# versao1.net
KiCad netlist of a schematic drawn in EAGLE
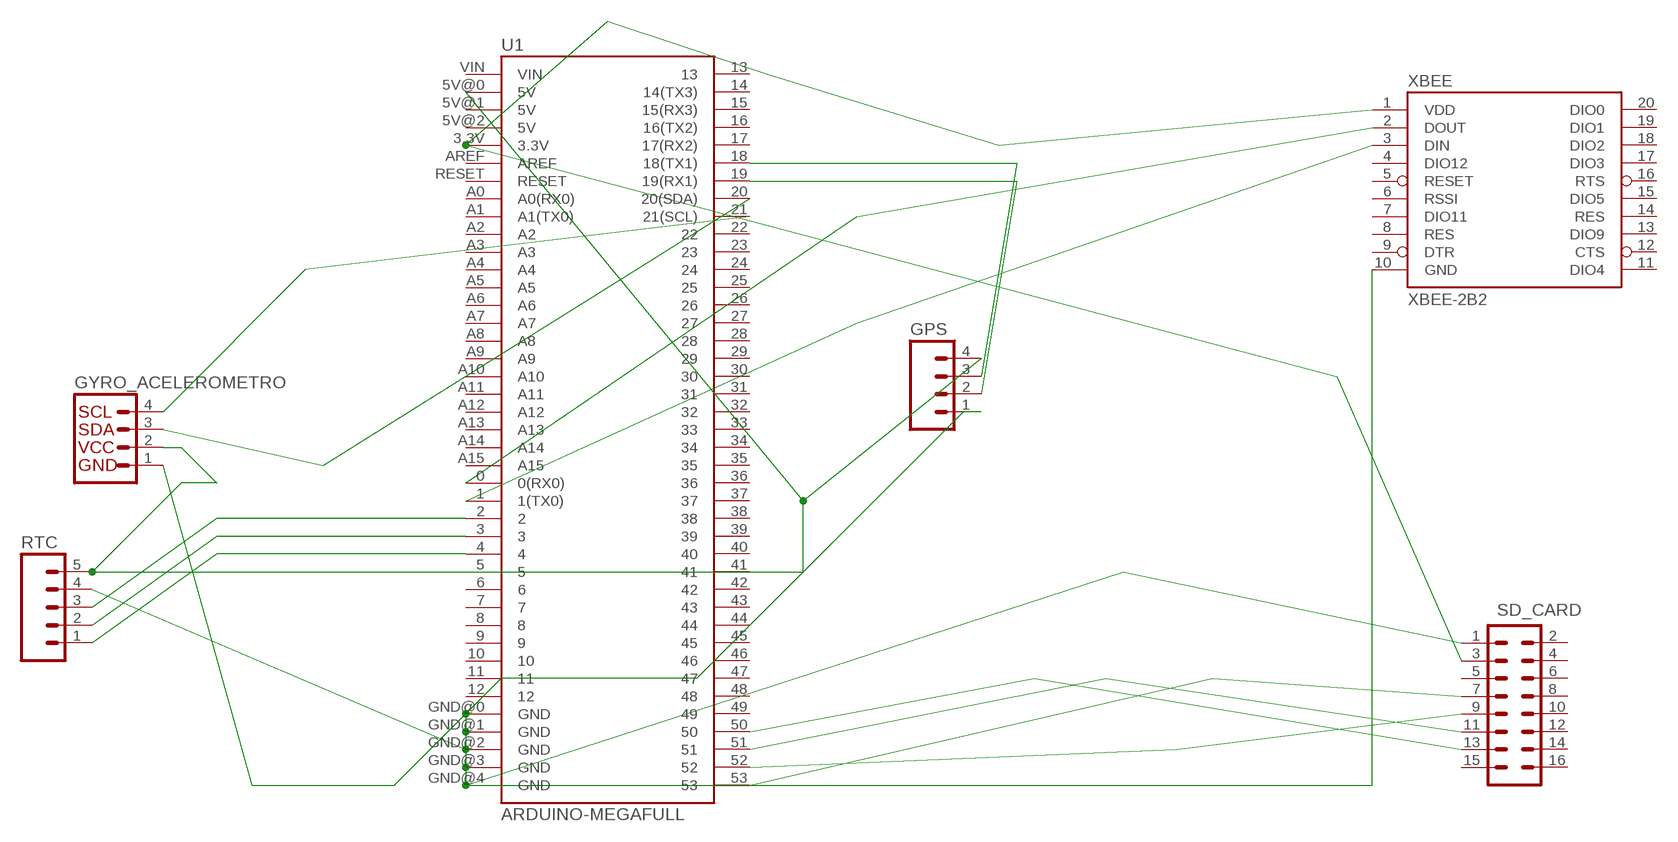
[diagram p0: schematic, sheet 1]

(export (version "E")
  (design (tool "Eeschema 10.0.6"))
  (components
    (comp (ref "GPS")
      (value "M04LOCK")
      (footprint "eagle-import:1X04_LOCK")
      (libsource (lib "eagle-import") (part "M04LOCK"))
    )
    (comp (ref "GYRO_ACELEROMETRO")
      (value "I2C_STANDARD")
      (footprint "eagle-import:1X04")
      (libsource (lib "eagle-import") (part "I2C_STANDARD"))
    )
    (comp (ref "RTC")
      (value "M05LOCK")
      (footprint "eagle-import:1X05_LOCK")
      (libsource (lib "eagle-import") (part "M05LOCK"))
    )
    (comp (ref "SD_CARD")
      (value "M08X2")
      (footprint "eagle-import:2X8")
      (libsource (lib "eagle-import") (part "M08X2"))
    )
    (comp (ref "U1")
      (value "ARDUINO-MEGAFULL")
      (footprint "eagle-import:ARDUINO_MEGA")
      (libsource (lib "eagle-import") (part "ARDUINO-MEGAFULL"))
    )
    (comp (ref "XBEE")
      (value "XBEE-2B2")
      (footprint "eagle-import:XBEE-SILK")
      (libsource (lib "eagle-import") (part "XBEE-2B2"))
    )
  )
  (nets
    (net (code "1") (name "Net-(GPS-Pad4)") (class "Default")
      (node (ref "GPS") (pin "4") (pinfunction "4_4") (pintype "passive"))
      (node (ref "GYRO_ACELEROMETRO") (pin "2") (pinfunction "2_2") (pintype "passive"))
      (node (ref "RTC") (pin "5") (pinfunction "5_5") (pintype "passive"))
      (node (ref "U1") (pin "5V@0") (pinfunction "5V_5V@0") (pintype "bidirectional"))
    )
    (net (code "2") (name "Net-(RTC-Pad1)") (class "Default")
      (node (ref "RTC") (pin "1") (pinfunction "1_1") (pintype "passive"))
      (node (ref "U1") (pin "4") (pinfunction "4_4") (pintype "bidirectional"))
    )
    (net (code "3") (name "Net-(RTC-Pad2)") (class "Default")
      (node (ref "RTC") (pin "2") (pinfunction "2_2") (pintype "passive"))
      (node (ref "U1") (pin "3") (pinfunction "3_3") (pintype "bidirectional"))
    )
    (net (code "4") (name "Net-(RTC-Pad3)") (class "Default")
      (node (ref "RTC") (pin "3") (pinfunction "3_3") (pintype "passive"))
      (node (ref "U1") (pin "2") (pinfunction "2_2") (pintype "bidirectional"))
    )
    (net (code "5") (name "Net-(SD_CARD-Pad7)") (class "Default")
      (node (ref "SD_CARD") (pin "7") (pinfunction "7_7") (pintype "passive"))
      (node (ref "U1") (pin "53") (pinfunction "53_53") (pintype "bidirectional"))
    )
    (net (code "6") (name "Net-(SD_CARD-Pad9)") (class "Default")
      (node (ref "SD_CARD") (pin "9") (pinfunction "9_9") (pintype "passive"))
      (node (ref "U1") (pin "52") (pinfunction "52_52") (pintype "bidirectional"))
    )
    (net (code "7") (name "Net-(SD_CARD-Pad11)") (class "Default")
      (node (ref "SD_CARD") (pin "11") (pinfunction "11_11") (pintype "passive"))
      (node (ref "U1") (pin "51") (pinfunction "51_51") (pintype "bidirectional"))
    )
    (net (code "8") (name "Net-(SD_CARD-Pad13)") (class "Default")
      (node (ref "SD_CARD") (pin "13") (pinfunction "13_13") (pintype "passive"))
      (node (ref "U1") (pin "50") (pinfunction "50_50") (pintype "bidirectional"))
    )
    (net (code "9") (name "Net-(U1-0(RX0))") (class "Default")
      (node (ref "U1") (pin "0") (pinfunction "0(RX0)_0") (pintype "bidirectional"))
      (node (ref "XBEE") (pin "2") (pinfunction "DOUT_2") (pintype "output"))
    )
    (net (code "10") (name "Net-(U1-1(TX0))") (class "Default")
      (node (ref "U1") (pin "1") (pinfunction "1(TX0)_1") (pintype "bidirectional"))
      (node (ref "XBEE") (pin "3") (pinfunction "DIN_3") (pintype "input"))
    )
    (net (code "11") (name "Net-(U1-18(TX1))") (class "Default")
      (node (ref "GPS") (pin "3") (pinfunction "3_3") (pintype "passive"))
      (node (ref "U1") (pin "18") (pinfunction "18(TX1)_18") (pintype "bidirectional"))
    )
    (net (code "12") (name "Net-(U1-19(RX1))") (class "Default")
      (node (ref "GPS") (pin "2") (pinfunction "2_2") (pintype "passive"))
      (node (ref "U1") (pin "19") (pinfunction "19(RX1)_19") (pintype "bidirectional"))
    )
    (net (code "13") (name "Net-(U1-20(SDA))") (class "Default")
      (node (ref "GYRO_ACELEROMETRO") (pin "3") (pinfunction "3_3") (pintype "passive"))
      (node (ref "U1") (pin "20") (pinfunction "20(SDA)_20") (pintype "bidirectional"))
    )
    (net (code "14") (name "Net-(U1-21(SCL))") (class "Default")
      (node (ref "GYRO_ACELEROMETRO") (pin "4") (pinfunction "4_4") (pintype "passive"))
      (node (ref "U1") (pin "21") (pinfunction "21(SCL)_21") (pintype "bidirectional"))
    )
    (net (code "15") (name "Net-(XBEE-GND)") (class "Default")
      (node (ref "GPS") (pin "1") (pinfunction "1_1") (pintype "passive"))
      (node (ref "GYRO_ACELEROMETRO") (pin "1") (pinfunction "1_1") (pintype "passive"))
      (node (ref "RTC") (pin "4") (pinfunction "4_4") (pintype "passive"))
      (node (ref "SD_CARD") (pin "1") (pinfunction "1_1") (pintype "passive"))
      (node (ref "U1") (pin "GND@0") (pinfunction "GND_GND@0") (pintype "bidirectional"))
      (node (ref "U1") (pin "GND@1") (pinfunction "GND_GND@1") (pintype "bidirectional"))
      (node (ref "U1") (pin "GND@2") (pinfunction "GND_GND@2") (pintype "bidirectional"))
      (node (ref "U1") (pin "GND@3") (pinfunction "GND_GND@3") (pintype "bidirectional"))
      (node (ref "U1") (pin "GND@4") (pinfunction "GND_GND@4") (pintype "bidirectional"))
      (node (ref "XBEE") (pin "10") (pinfunction "GND_10") (pintype "power_in"))
    )
    (net (code "16") (name "Net-(XBEE-VDD)") (class "Default")
      (node (ref "SD_CARD") (pin "3") (pinfunction "3_3") (pintype "passive"))
      (node (ref "U1") (pin "3.3V") (pinfunction "3.3V_3.3V") (pintype "bidirectional"))
      (node (ref "XBEE") (pin "1") (pinfunction "VDD_1") (pintype "power_in"))
    )
    (net (code "17") (name "unconnected-(SD_CARD-Pad2)") (class "Default")
      (node (ref "SD_CARD") (pin "2") (pinfunction "2_2") (pintype "passive"))
    )
    (net (code "18") (name "unconnected-(SD_CARD-Pad4)") (class "Default")
      (node (ref "SD_CARD") (pin "4") (pinfunction "4_4") (pintype "passive"))
    )
    (net (code "19") (name "unconnected-(SD_CARD-Pad5)") (class "Default")
      (node (ref "SD_CARD") (pin "5") (pinfunction "5_5") (pintype "passive"))
    )
    (net (code "20") (name "unconnected-(SD_CARD-Pad6)") (class "Default")
      (node (ref "SD_CARD") (pin "6") (pinfunction "6_6") (pintype "passive"))
    )
    (net (code "21") (name "unconnected-(SD_CARD-Pad8)") (class "Default")
      (node (ref "SD_CARD") (pin "8") (pinfunction "8_8") (pintype "passive"))
    )
    (net (code "22") (name "unconnected-(SD_CARD-Pad10)") (class "Default")
      (node (ref "SD_CARD") (pin "10") (pinfunction "10_10") (pintype "passive"))
    )
    (net (code "23") (name "unconnected-(SD_CARD-Pad12)") (class "Default")
      (node (ref "SD_CARD") (pin "12") (pinfunction "12_12") (pintype "passive"))
    )
    (net (code "24") (name "unconnected-(SD_CARD-Pad14)") (class "Default")
      (node (ref "SD_CARD") (pin "14") (pinfunction "14_14") (pintype "passive"))
    )
    (net (code "25") (name "unconnected-(SD_CARD-Pad15)") (class "Default")
      (node (ref "SD_CARD") (pin "15") (pinfunction "15_15") (pintype "passive"))
    )
    (net (code "26") (name "unconnected-(SD_CARD-Pad16)") (class "Default")
      (node (ref "SD_CARD") (pin "16") (pinfunction "16_16") (pintype "passive"))
    )
    (net (code "27") (name "unconnected-(U1-5V-Pad5V@1)") (class "Default")
      (node (ref "U1") (pin "5V@1") (pinfunction "5V_5V@1") (pintype "bidirectional"))
    )
    (net (code "28") (name "unconnected-(U1-5V-Pad5V@2)") (class "Default")
      (node (ref "U1") (pin "5V@2") (pinfunction "5V_5V@2") (pintype "bidirectional"))
    )
    (net (code "29") (name "unconnected-(U1-14(TX3)-Pad14)") (class "Default")
      (node (ref "U1") (pin "14") (pinfunction "14(TX3)_14") (pintype "bidirectional"))
    )
    (net (code "30") (name "unconnected-(U1-15(RX3)-Pad15)") (class "Default")
      (node (ref "U1") (pin "15") (pinfunction "15(RX3)_15") (pintype "bidirectional"))
    )
    (net (code "31") (name "unconnected-(U1-16(TX2)-Pad16)") (class "Default")
      (node (ref "U1") (pin "16") (pinfunction "16(TX2)_16") (pintype "bidirectional"))
    )
    (net (code "32") (name "unconnected-(U1-17(RX2)-Pad17)") (class "Default")
      (node (ref "U1") (pin "17") (pinfunction "17(RX2)_17") (pintype "bidirectional"))
    )
    (net (code "33") (name "unconnected-(U1-A0(RX0)-PadA0)") (class "Default")
      (node (ref "U1") (pin "A0") (pinfunction "A0(RX0)_A0") (pintype "bidirectional"))
    )
    (net (code "34") (name "unconnected-(U1-A1(TX0)-PadA1)") (class "Default")
      (node (ref "U1") (pin "A1") (pinfunction "A1(TX0)_A1") (pintype "bidirectional"))
    )
    (net (code "35") (name "unconnected-(U1-Pad5)") (class "Default")
      (node (ref "U1") (pin "5") (pinfunction "5_5") (pintype "bidirectional"))
    )
    (net (code "36") (name "unconnected-(U1-Pad6)") (class "Default")
      (node (ref "U1") (pin "6") (pinfunction "6_6") (pintype "bidirectional"))
    )
    (net (code "37") (name "unconnected-(U1-Pad7)") (class "Default")
      (node (ref "U1") (pin "7") (pinfunction "7_7") (pintype "bidirectional"))
    )
    (net (code "38") (name "unconnected-(U1-Pad8)") (class "Default")
      (node (ref "U1") (pin "8") (pinfunction "8_8") (pintype "bidirectional"))
    )
    (net (code "39") (name "unconnected-(U1-Pad9)") (class "Default")
      (node (ref "U1") (pin "9") (pinfunction "9_9") (pintype "bidirectional"))
    )
    (net (code "40") (name "unconnected-(U1-Pad10)") (class "Default")
      (node (ref "U1") (pin "10") (pinfunction "10_10") (pintype "bidirectional"))
    )
    (net (code "41") (name "unconnected-(U1-Pad11)") (class "Default")
      (node (ref "U1") (pin "11") (pinfunction "11_11") (pintype "bidirectional"))
    )
    (net (code "42") (name "unconnected-(U1-Pad12)") (class "Default")
      (node (ref "U1") (pin "12") (pinfunction "12_12") (pintype "bidirectional"))
    )
    (net (code "43") (name "unconnected-(U1-Pad13)") (class "Default")
      (node (ref "U1") (pin "13") (pinfunction "13_13") (pintype "bidirectional"))
    )
    (net (code "44") (name "unconnected-(U1-Pad22)") (class "Default")
      (node (ref "U1") (pin "22") (pinfunction "22_22") (pintype "bidirectional"))
    )
    (net (code "45") (name "unconnected-(U1-Pad23)") (class "Default")
      (node (ref "U1") (pin "23") (pinfunction "23_23") (pintype "bidirectional"))
    )
    (net (code "46") (name "unconnected-(U1-Pad24)") (class "Default")
      (node (ref "U1") (pin "24") (pinfunction "24_24") (pintype "bidirectional"))
    )
    (net (code "47") (name "unconnected-(U1-Pad25)") (class "Default")
      (node (ref "U1") (pin "25") (pinfunction "25_25") (pintype "bidirectional"))
    )
    (net (code "48") (name "unconnected-(U1-Pad26)") (class "Default")
      (node (ref "U1") (pin "26") (pinfunction "26_26") (pintype "bidirectional"))
    )
    (net (code "49") (name "unconnected-(U1-Pad27)") (class "Default")
      (node (ref "U1") (pin "27") (pinfunction "27_27") (pintype "bidirectional"))
    )
    (net (code "50") (name "unconnected-(U1-Pad28)") (class "Default")
      (node (ref "U1") (pin "28") (pinfunction "28_28") (pintype "bidirectional"))
    )
    (net (code "51") (name "unconnected-(U1-Pad29)") (class "Default")
      (node (ref "U1") (pin "29") (pinfunction "29_29") (pintype "bidirectional"))
    )
    (net (code "52") (name "unconnected-(U1-Pad30)") (class "Default")
      (node (ref "U1") (pin "30") (pinfunction "30_30") (pintype "bidirectional"))
    )
    (net (code "53") (name "unconnected-(U1-Pad31)") (class "Default")
      (node (ref "U1") (pin "31") (pinfunction "31_31") (pintype "bidirectional"))
    )
    (net (code "54") (name "unconnected-(U1-Pad32)") (class "Default")
      (node (ref "U1") (pin "32") (pinfunction "32_32") (pintype "bidirectional"))
    )
    (net (code "55") (name "unconnected-(U1-Pad33)") (class "Default")
      (node (ref "U1") (pin "33") (pinfunction "33_33") (pintype "bidirectional"))
    )
    (net (code "56") (name "unconnected-(U1-Pad34)") (class "Default")
      (node (ref "U1") (pin "34") (pinfunction "34_34") (pintype "bidirectional"))
    )
    (net (code "57") (name "unconnected-(U1-Pad35)") (class "Default")
      (node (ref "U1") (pin "35") (pinfunction "35_35") (pintype "bidirectional"))
    )
    (net (code "58") (name "unconnected-(U1-Pad36)") (class "Default")
      (node (ref "U1") (pin "36") (pinfunction "36_36") (pintype "bidirectional"))
    )
    (net (code "59") (name "unconnected-(U1-Pad37)") (class "Default")
      (node (ref "U1") (pin "37") (pinfunction "37_37") (pintype "bidirectional"))
    )
    (net (code "60") (name "unconnected-(U1-Pad38)") (class "Default")
      (node (ref "U1") (pin "38") (pinfunction "38_38") (pintype "bidirectional"))
    )
    (net (code "61") (name "unconnected-(U1-Pad39)") (class "Default")
      (node (ref "U1") (pin "39") (pinfunction "39_39") (pintype "bidirectional"))
    )
    (net (code "62") (name "unconnected-(U1-Pad40)") (class "Default")
      (node (ref "U1") (pin "40") (pinfunction "40_40") (pintype "bidirectional"))
    )
    (net (code "63") (name "unconnected-(U1-Pad41)") (class "Default")
      (node (ref "U1") (pin "41") (pinfunction "41_41") (pintype "bidirectional"))
    )
    (net (code "64") (name "unconnected-(U1-Pad42)") (class "Default")
      (node (ref "U1") (pin "42") (pinfunction "42_42") (pintype "bidirectional"))
    )
    (net (code "65") (name "unconnected-(U1-Pad43)") (class "Default")
      (node (ref "U1") (pin "43") (pinfunction "43_43") (pintype "bidirectional"))
    )
    (net (code "66") (name "unconnected-(U1-Pad44)") (class "Default")
      (node (ref "U1") (pin "44") (pinfunction "44_44") (pintype "bidirectional"))
    )
    (net (code "67") (name "unconnected-(U1-Pad45)") (class "Default")
      (node (ref "U1") (pin "45") (pinfunction "45_45") (pintype "bidirectional"))
    )
    (net (code "68") (name "unconnected-(U1-Pad46)") (class "Default")
      (node (ref "U1") (pin "46") (pinfunction "46_46") (pintype "bidirectional"))
    )
    (net (code "69") (name "unconnected-(U1-Pad47)") (class "Default")
      (node (ref "U1") (pin "47") (pinfunction "47_47") (pintype "bidirectional"))
    )
    (net (code "70") (name "unconnected-(U1-Pad48)") (class "Default")
      (node (ref "U1") (pin "48") (pinfunction "48_48") (pintype "bidirectional"))
    )
    (net (code "71") (name "unconnected-(U1-Pad49)") (class "Default")
      (node (ref "U1") (pin "49") (pinfunction "49_49") (pintype "bidirectional"))
    )
    (net (code "72") (name "unconnected-(U1-PadA2)") (class "Default")
      (node (ref "U1") (pin "A2") (pinfunction "A2_A2") (pintype "bidirectional"))
    )
    (net (code "73") (name "unconnected-(U1-PadA3)") (class "Default")
      (node (ref "U1") (pin "A3") (pinfunction "A3_A3") (pintype "bidirectional"))
    )
    (net (code "74") (name "unconnected-(U1-PadA4)") (class "Default")
      (node (ref "U1") (pin "A4") (pinfunction "A4_A4") (pintype "bidirectional"))
    )
    (net (code "75") (name "unconnected-(U1-PadA5)") (class "Default")
      (node (ref "U1") (pin "A5") (pinfunction "A5_A5") (pintype "bidirectional"))
    )
    (net (code "76") (name "unconnected-(U1-PadA6)") (class "Default")
      (node (ref "U1") (pin "A6") (pinfunction "A6_A6") (pintype "bidirectional"))
    )
    (net (code "77") (name "unconnected-(U1-PadA7)") (class "Default")
      (node (ref "U1") (pin "A7") (pinfunction "A7_A7") (pintype "bidirectional"))
    )
    (net (code "78") (name "unconnected-(U1-PadA8)") (class "Default")
      (node (ref "U1") (pin "A8") (pinfunction "A8_A8") (pintype "bidirectional"))
    )
    (net (code "79") (name "unconnected-(U1-PadA9)") (class "Default")
      (node (ref "U1") (pin "A9") (pinfunction "A9_A9") (pintype "bidirectional"))
    )
    (net (code "80") (name "unconnected-(U1-PadA10)") (class "Default")
      (node (ref "U1") (pin "A10") (pinfunction "A10_A10") (pintype "bidirectional"))
    )
    (net (code "81") (name "unconnected-(U1-PadA11)") (class "Default")
      (node (ref "U1") (pin "A11") (pinfunction "A11_A11") (pintype "bidirectional"))
    )
    (net (code "82") (name "unconnected-(U1-PadA12)") (class "Default")
      (node (ref "U1") (pin "A12") (pinfunction "A12_A12") (pintype "bidirectional"))
    )
    (net (code "83") (name "unconnected-(U1-PadA13)") (class "Default")
      (node (ref "U1") (pin "A13") (pinfunction "A13_A13") (pintype "bidirectional"))
    )
    (net (code "84") (name "unconnected-(U1-PadA14)") (class "Default")
      (node (ref "U1") (pin "A14") (pinfunction "A14_A14") (pintype "bidirectional"))
    )
    (net (code "85") (name "unconnected-(U1-PadA15)") (class "Default")
      (node (ref "U1") (pin "A15") (pinfunction "A15_A15") (pintype "bidirectional"))
    )
    (net (code "86") (name "unconnected-(U1-PadAREF)") (class "Default")
      (node (ref "U1") (pin "AREF") (pinfunction "AREF_AREF") (pintype "bidirectional"))
    )
    (net (code "87") (name "unconnected-(U1-PadRESET)") (class "Default")
      (node (ref "U1") (pin "RESET") (pinfunction "RESET_RESET") (pintype "bidirectional"))
    )
    (net (code "88") (name "unconnected-(U1-PadVIN)") (class "Default")
      (node (ref "U1") (pin "VIN") (pinfunction "VIN_VIN") (pintype "bidirectional"))
    )
    (net (code "89") (name "unconnected-(XBEE-CTS-Pad12)") (class "Default")
      (node (ref "XBEE") (pin "12") (pinfunction "CTS_12") (pintype "output"))
    )
    (net (code "90") (name "unconnected-(XBEE-DIO0-Pad20)") (class "Default")
      (node (ref "XBEE") (pin "20") (pinfunction "DIO0_20") (pintype "bidirectional"))
    )
    (net (code "91") (name "unconnected-(XBEE-DIO1-Pad19)") (class "Default")
      (node (ref "XBEE") (pin "19") (pinfunction "DIO1_19") (pintype "bidirectional"))
    )
    (net (code "92") (name "unconnected-(XBEE-DIO2-Pad18)") (class "Default")
      (node (ref "XBEE") (pin "18") (pinfunction "DIO2_18") (pintype "bidirectional"))
    )
    (net (code "93") (name "unconnected-(XBEE-DIO3-Pad17)") (class "Default")
      (node (ref "XBEE") (pin "17") (pinfunction "DIO3_17") (pintype "bidirectional"))
    )
    (net (code "94") (name "unconnected-(XBEE-DIO4-Pad11)") (class "Default")
      (node (ref "XBEE") (pin "11") (pinfunction "DIO4_11") (pintype "bidirectional"))
    )
    (net (code "95") (name "unconnected-(XBEE-DIO5-Pad15)") (class "Default")
      (node (ref "XBEE") (pin "15") (pinfunction "DIO5_15") (pintype "bidirectional"))
    )
    (net (code "96") (name "unconnected-(XBEE-DIO9-Pad13)") (class "Default")
      (node (ref "XBEE") (pin "13") (pinfunction "DIO9_13") (pintype "bidirectional"))
    )
    (net (code "97") (name "unconnected-(XBEE-DIO11-Pad7)") (class "Default")
      (node (ref "XBEE") (pin "7") (pinfunction "DIO11_7") (pintype "bidirectional"))
    )
    (net (code "98") (name "unconnected-(XBEE-DIO12-Pad4)") (class "Default")
      (node (ref "XBEE") (pin "4") (pinfunction "DIO12_4") (pintype "bidirectional"))
    )
    (net (code "99") (name "unconnected-(XBEE-DTR-Pad9)") (class "Default")
      (node (ref "XBEE") (pin "9") (pinfunction "DTR_9") (pintype "bidirectional"))
    )
    (net (code "100") (name "unconnected-(XBEE-RES-Pad8)") (class "Default")
      (node (ref "XBEE") (pin "8") (pinfunction "RES_8") (pintype "bidirectional"))
    )
    (net (code "101") (name "unconnected-(XBEE-RES-Pad14)") (class "Default")
      (node (ref "XBEE") (pin "14") (pinfunction "RES_14") (pintype "bidirectional"))
    )
    (net (code "102") (name "unconnected-(XBEE-RESET-Pad5)") (class "Default")
      (node (ref "XBEE") (pin "5") (pinfunction "RESET_5") (pintype "input"))
    )
    (net (code "103") (name "unconnected-(XBEE-RSSI-Pad6)") (class "Default")
      (node (ref "XBEE") (pin "6") (pinfunction "RSSI_6") (pintype "bidirectional"))
    )
    (net (code "104") (name "unconnected-(XBEE-RTS-Pad16)") (class "Default")
      (node (ref "XBEE") (pin "16") (pinfunction "RTS_16") (pintype "input"))
    )
  )
)
